# 12V_POWER_BULKHEAD.net
KiCad netlist of a schematic drawn in Altium Designer
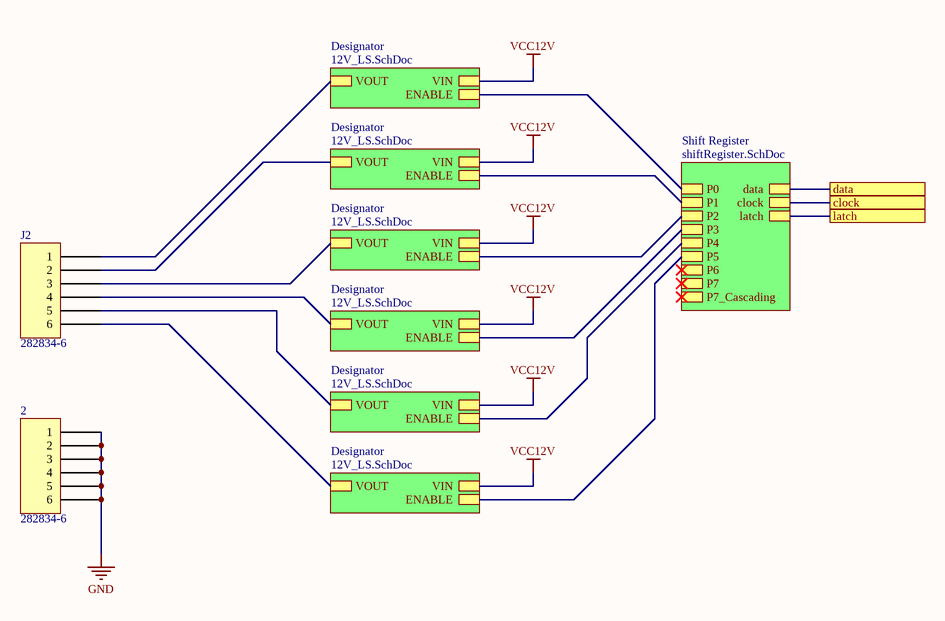
[diagram p0: 12V_POWER_BULKHEAD.SchDoc]

(export (version "E")
  (design (tool "Eeschema 10.0.6"))
  (components
    (comp (ref "2")
      (value "282834-6")
      (footprint "TE 282834-6")
      (description "TERM BLK 6P SIDE ENT 2.54MM PCB")
      (fields (field (name "MANUFACTURER") "TE Connectivity AMP Connectors") (field (name "VOLTAGE") "150V"))
      (libsource (lib "Celestial Altium Library - altium_library") (part "6 Pin"))
    )
    (comp (ref "J2")
      (value "282834-6")
      (footprint "TE 282834-6")
      (description "TERM BLK 6P SIDE ENT 2.54MM PCB")
      (fields (field (name "MANUFACTURER") "TE Connectivity AMP Connectors") (field (name "VOLTAGE") "150V"))
      (libsource (lib "Celestial Altium Library - altium_library") (part "6 Pin"))
    )
  )
  (nets
    (net (code "10") (name "/VOUT") (class "Default")
      (node (ref "J2") (pin "4") (pinfunction "4_4") (pintype "passive"))
    )
    (net (code "11") (name "/VOUT_1") (class "Default")
      (node (ref "J2") (pin "1") (pinfunction "1_1") (pintype "passive"))
    )
    (net (code "12") (name "/VOUT_2") (class "Default")
      (node (ref "J2") (pin "2") (pinfunction "2_2") (pintype "passive"))
    )
    (net (code "13") (name "/VOUT_3") (class "Default")
      (node (ref "J2") (pin "3") (pinfunction "3_3") (pintype "passive"))
    )
    (net (code "14") (name "/VOUT_4") (class "Default")
      (node (ref "J2") (pin "5") (pinfunction "5_5") (pintype "passive"))
    )
    (net (code "15") (name "/VOUT_5") (class "Default")
      (node (ref "J2") (pin "6") (pinfunction "6_6") (pintype "passive"))
    )
    (net (code "19") (name "GND") (class "Default")
      (node (ref "2") (pin "1") (pinfunction "1_1") (pintype "passive"))
      (node (ref "2") (pin "2") (pinfunction "2_2") (pintype "passive"))
      (node (ref "2") (pin "3") (pinfunction "3_3") (pintype "passive"))
      (node (ref "2") (pin "4") (pinfunction "4_4") (pintype "passive"))
      (node (ref "2") (pin "5") (pinfunction "5_5") (pintype "passive"))
      (node (ref "2") (pin "6") (pinfunction "6_6") (pintype "passive"))
    )
  )
)
